# 11-POWER-P12V.net
KiCad netlist of a schematic drawn in Altium Designer
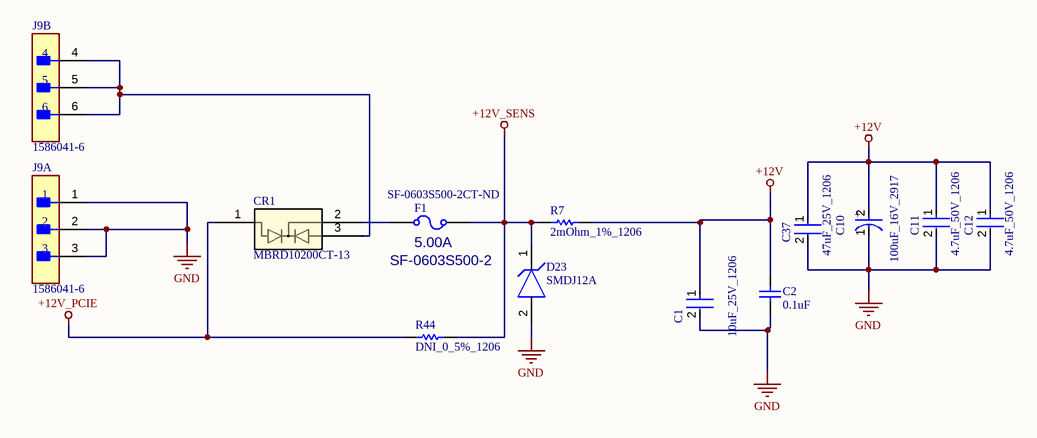
[diagram p0: 11-POWER-P12V.SchDoc]

(export (version "E")
  (design (tool "Eeschema 10.0.6"))
  (components
    (comp (ref "C1")
      (value "10uF_25V_1206")
      (footprint "FP-MK316L-MFG")
      (description "CAP CER 10UF 25V X7R 1206")
      (fields (field (name "TOLERANCE") "10%"))
      (libsource (lib "Altium Content Vault") (part "11868f565c42a9108669ba33697ecf6"))
    )
    (comp (ref "C2")
      (value "0.1uF")
      (footprint "CAPC1608X87X45ML20T05")
      (description "C0603X104K5RACAUTO")
      (fields (field (name "MANUFACTURER") "Kemet"))
      (libsource (lib "Altium Content Vault") (part "CAP"))
    )
    (comp (ref "C10")
      (value "100uF_16V_2917")
      (footprint "FP-T495D107K016ATE125-MFG")
      (description "CAP TANT 100UF 10% 16V 2917")
      (fields (field (name "VOLTAGE") "16V") (field (name "TOLERANCE") "10%"))
      (libsource (lib "Altium Content Vault") (part "a00bbbee19879c290e62620ae7e47b1"))
    )
    (comp (ref "C11")
      (value "4.7uF_50V_1206")
      (footprint "FP-GRM31C-0_2-e0_3_0_8-IPC_C")
      (description "Chip Multilayer Ceramic Capacitors for General Purpose, 1206, 4.7uF, X7R, 15%, 10%, 50V")
      (fields (field (name "VOLTAGE") "50V") (field (name "TOLERANCE") "10%"))
      (libsource (lib "Altium Content Vault") (part "02cd4be3c70576c341d710602a673aa"))
    )
    (comp (ref "C12")
      (value "4.7uF_50V_1206")
      (footprint "FP-GRM31C-0_2-e0_3_0_8-IPC_C")
      (description "Chip Multilayer Ceramic Capacitors for General Purpose, 1206, 4.7uF, X7R, 15%, 10%, 50V")
      (fields (field (name "VOLTAGE") "50V") (field (name "TOLERANCE") "10%"))
      (libsource (lib "Altium Content Vault") (part "02cd4be3c70576c341d710602a673aa"))
    )
    (comp (ref "C37")
      (value "47uF_25V_1206")
      (footprint "FP-C3216-160-0_2-MFG")
      (description "Multilayer Ceramic Capacitors 47uF ±20% 25V X5R SMD 1206")
      (fields (field (name "VOLTAGE") "25V") (field (name "TOLERANCE") "20%"))
      (libsource (lib "Altium Content Vault") (part "11868f565c42a9108669ba33697ecf6"))
    )
    (comp (ref "CR1")
      (value "MBRD10200CT-13")
      (footprint "TO252(DPAK)_DIO")
      (description "No Description Available")
      (libsource (lib "MBRD10200CT-13") (part "MBRD10200CT-13"))
    )
    (comp (ref "D23")
      (value "SMDJ12A")
      (footprint "FP-DO-214AB_SMC_J-Bend-MFG")
      (description "TVS DIODE 12V 19.9V DO214AB")
      (libsource (lib "Altium Content Vault") (part "673ecd2ea4d7fb87b4005b0cb348b7d"))
    )
    (comp (ref "F1")
      (value "5.00A")
      (footprint "FUSM1608X60N")
      (description "FUSE SLOW 5.00A 32V M 0603")
      (fields
        (field (name "MFG PART NUM") "SF-0603S500-2")
        (field (name "VALENTIUM PART NUM") "<VALENTIUM>")
        (field (name "SUPPLIER PART NUMBER 1") "SF-0603S500-2CT-ND")
        (field (name "Comment") "FUSE_0603_5.00A")
      )
      (libsource (lib "Passives") (part "FUSE_0603_2.00A"))
    )
    (comp (ref "J9")
      (value "1586041-6")
      (footprint "FP-1586041-6-MFG")
      (description "CONN HEADER R/A 6POS 4.2MM")
      (fields
        (field (name "OCTOPART") "https://octopart.com/1586041-6-te+connectivity-46514050")
        (field (name "MANUFACTURER") "TE")
      )
      (libsource (lib "Altium Content Vault") (part "bb9cbdb24149a20ba329b4e86909569"))
    )
    (comp (ref "R7")
      (value "2mOhm_1%_1206")
      (footprint "RESC3216X89X64NL25T25")
      (fields (field (name "MANUFACTURER") "Vishay Dale") (field (name "PART NUMBER") "WSL12062L000FEA18"))
      (libsource (lib "Altium Content Vault") (part "RES"))
    )
    (comp (ref "R44")
      (value "DNI_0_5%_1206")
      (footprint "RESC3116X65X50ML20T20")
      (fields (field (name "PART NUMBER") "CRCW12060000Z0EAHP") (field (name "MANUFACTURER") "Vishay Dale"))
      (libsource (lib "Altium Content Vault") (part "RES"))
    )
  )
  (nets
    (net (code "1") (name "+12V") (class "Default")
      (node (ref "C1") (pin "1") (pinfunction "1_1") (pintype "passive"))
      (node (ref "C10") (pin "2") (pinfunction "A_2") (pintype "passive"))
      (node (ref "C11") (pin "1") (pinfunction "1_1") (pintype "passive"))
      (node (ref "C12") (pin "1") (pinfunction "1_1") (pintype "passive"))
      (node (ref "C2") (pin "2") (pinfunction "2_2") (pintype "passive"))
      (node (ref "C37") (pin "1") (pinfunction "1_1") (pintype "passive"))
      (node (ref "R7") (pin "2") (pinfunction "2_2") (pintype "passive"))
    )
    (net (code "2") (name "+12V_PCIE") (class "Default")
      (node (ref "CR1") (pin "1") (pinfunction "1_1") (pintype "passive"))
      (node (ref "R44") (pin "1") (pinfunction "1_1") (pintype "passive"))
    )
    (net (code "3") (name "+12V_SENS") (class "Default")
      (node (ref "D23") (pin "1") (pinfunction "C_1") (pintype "passive"))
      (node (ref "F1") (pin "2") (pinfunction "2_2") (pintype "passive"))
      (node (ref "R44") (pin "2") (pinfunction "2_2") (pintype "passive"))
      (node (ref "R7") (pin "1") (pinfunction "1_1") (pintype "passive"))
    )
    (net (code "4") (name "GND") (class "Default")
      (node (ref "C1") (pin "2") (pinfunction "2_2") (pintype "passive"))
      (node (ref "C10") (pin "1") (pinfunction "C_1") (pintype "passive"))
      (node (ref "C11") (pin "2") (pinfunction "2_2") (pintype "passive"))
      (node (ref "C12") (pin "2") (pinfunction "2_2") (pintype "passive"))
      (node (ref "C2") (pin "1") (pinfunction "1_1") (pintype "passive"))
      (node (ref "C37") (pin "2") (pinfunction "2_2") (pintype "passive"))
      (node (ref "D23") (pin "2") (pinfunction "A_2") (pintype "passive"))
      (node (ref "J9") (pin "1") (pinfunction "1_1") (pintype "passive"))
      (node (ref "J9") (pin "2") (pinfunction "2_2") (pintype "passive"))
      (node (ref "J9") (pin "3") (pinfunction "3_3") (pintype "passive"))
    )
    (net (code "5") (name "Net-(CR1-Pad2)") (class "Default")
      (node (ref "CR1") (pin "2") (pinfunction "2_2") (pintype "passive"))
      (node (ref "F1") (pin "1") (pinfunction "1_1") (pintype "passive"))
    )
    (net (code "6") (name "Net-(CR1-Pad3)") (class "Default")
      (node (ref "CR1") (pin "3") (pinfunction "3_3") (pintype "passive"))
      (node (ref "J9") (pin "4") (pinfunction "4_4") (pintype "passive"))
      (node (ref "J9") (pin "5") (pinfunction "5_5") (pintype "passive"))
      (node (ref "J9") (pin "6") (pinfunction "6_6") (pintype "passive"))
    )
  )
)
